# Xmas_A_board.net
KiCad netlist of a schematic drawn in EAGLE
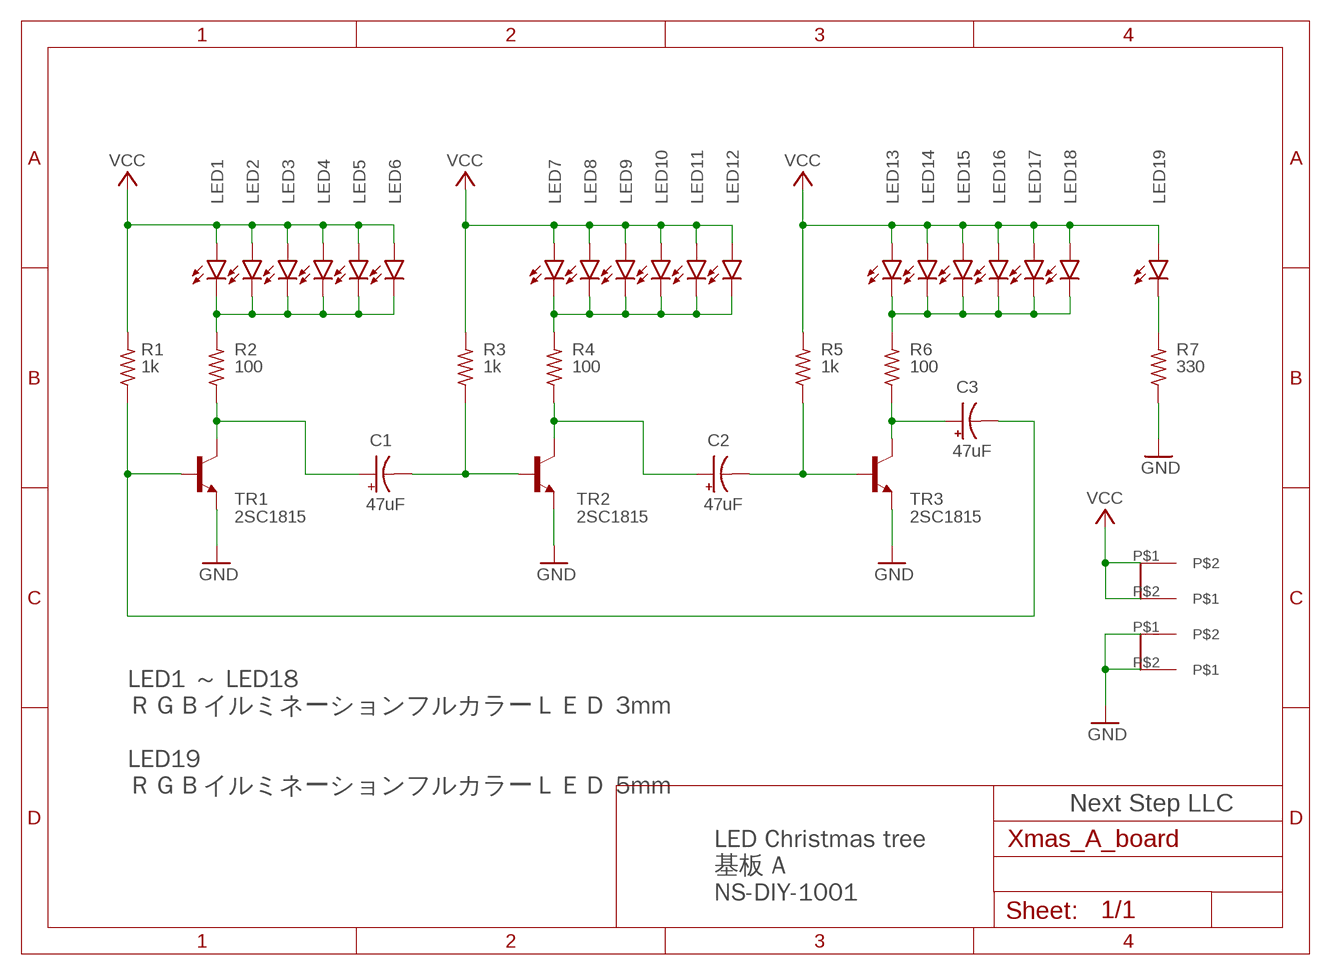
[diagram p0: schematic, sheet 1]

(export (version "E")
  (design (tool "Eeschema 10.0.6"))
  (components
    (comp (ref "C1")
      (value "47uF")
      (footprint "eagle-import:E2-4")
      (libsource (lib "eagle-import") (part "CPOL-USE2-4"))
    )
    (comp (ref "C2")
      (value "47uF")
      (footprint "eagle-import:E2-4")
      (libsource (lib "eagle-import") (part "CPOL-USE2-4"))
    )
    (comp (ref "C3")
      (value "47uF")
      (footprint "eagle-import:E2-4")
      (libsource (lib "eagle-import") (part "CPOL-USE2-4"))
    )
    (comp (ref "LED1")
      (value "LED3MM")
      (footprint "eagle-import:LED3MM")
      (libsource (lib "eagle-import") (part "LED3MM"))
    )
    (comp (ref "LED2")
      (value "LED3MM")
      (footprint "eagle-import:LED3MM")
      (libsource (lib "eagle-import") (part "LED3MM"))
    )
    (comp (ref "LED3")
      (value "LED3MM")
      (footprint "eagle-import:LED3MM")
      (libsource (lib "eagle-import") (part "LED3MM"))
    )
    (comp (ref "LED4")
      (value "LED3MM")
      (footprint "eagle-import:LED3MM")
      (libsource (lib "eagle-import") (part "LED3MM"))
    )
    (comp (ref "LED5")
      (value "LED3MM")
      (footprint "eagle-import:LED3MM")
      (libsource (lib "eagle-import") (part "LED3MM"))
    )
    (comp (ref "LED6")
      (value "LED3MM")
      (footprint "eagle-import:LED3MM")
      (libsource (lib "eagle-import") (part "LED3MM"))
    )
    (comp (ref "LED7")
      (value "LED3MM")
      (footprint "eagle-import:LED3MM")
      (libsource (lib "eagle-import") (part "LED3MM"))
    )
    (comp (ref "LED8")
      (value "LED3MM")
      (footprint "eagle-import:LED3MM")
      (libsource (lib "eagle-import") (part "LED3MM"))
    )
    (comp (ref "LED9")
      (value "LED3MM")
      (footprint "eagle-import:LED3MM")
      (libsource (lib "eagle-import") (part "LED3MM"))
    )
    (comp (ref "LED10")
      (value "LED3MM")
      (footprint "eagle-import:LED3MM")
      (libsource (lib "eagle-import") (part "LED3MM"))
    )
    (comp (ref "LED11")
      (value "LED3MM")
      (footprint "eagle-import:LED3MM")
      (libsource (lib "eagle-import") (part "LED3MM"))
    )
    (comp (ref "LED12")
      (value "LED3MM")
      (footprint "eagle-import:LED3MM")
      (libsource (lib "eagle-import") (part "LED3MM"))
    )
    (comp (ref "LED13")
      (value "LED3MM")
      (footprint "eagle-import:LED3MM")
      (libsource (lib "eagle-import") (part "LED3MM"))
    )
    (comp (ref "LED14")
      (value "LED3MM")
      (footprint "eagle-import:LED3MM")
      (libsource (lib "eagle-import") (part "LED3MM"))
    )
    (comp (ref "LED15")
      (value "LED3MM")
      (footprint "eagle-import:LED3MM")
      (libsource (lib "eagle-import") (part "LED3MM"))
    )
    (comp (ref "LED16")
      (value "LED3MM")
      (footprint "eagle-import:LED3MM")
      (libsource (lib "eagle-import") (part "LED3MM"))
    )
    (comp (ref "LED17")
      (value "LED3MM")
      (footprint "eagle-import:LED3MM")
      (libsource (lib "eagle-import") (part "LED3MM"))
    )
    (comp (ref "LED18")
      (value "LED3MM")
      (footprint "eagle-import:LED3MM")
      (libsource (lib "eagle-import") (part "LED3MM"))
    )
    (comp (ref "LED19")
      (value "LED5MM")
      (footprint "eagle-import:LED5MM")
      (libsource (lib "eagle-import") (part "LED5MM"))
    )
    (comp (ref "R1")
      (value "1k")
      (footprint "eagle-import:0204_7")
      (libsource (lib "eagle-import") (part "R-US_0204/7"))
    )
    (comp (ref "R2")
      (value "100")
      (footprint "eagle-import:0204_7")
      (libsource (lib "eagle-import") (part "R-US_0204/7"))
    )
    (comp (ref "R3")
      (value "1k")
      (footprint "eagle-import:0204_7")
      (libsource (lib "eagle-import") (part "R-US_0204/7"))
    )
    (comp (ref "R4")
      (value "100")
      (footprint "eagle-import:0204_7")
      (libsource (lib "eagle-import") (part "R-US_0204/7"))
    )
    (comp (ref "R5")
      (value "1k")
      (footprint "eagle-import:0204_7")
      (libsource (lib "eagle-import") (part "R-US_0204/7"))
    )
    (comp (ref "R6")
      (value "100")
      (footprint "eagle-import:0204_7")
      (libsource (lib "eagle-import") (part "R-US_0204/7"))
    )
    (comp (ref "R7")
      (value "330")
      (footprint "eagle-import:0204_7")
      (libsource (lib "eagle-import") (part "R-US_0204/7"))
    )
    (comp (ref "TR1")
      (value "2SC1815")
      (footprint "eagle-import:TO92-ECB")
      (libsource (lib "eagle-import") (part "2SC1815"))
    )
    (comp (ref "TR2")
      (value "2SC1815")
      (footprint "eagle-import:TO92-ECB")
      (libsource (lib "eagle-import") (part "2SC1815"))
    )
    (comp (ref "TR3")
      (value "2SC1815")
      (footprint "eagle-import:TO92-ECB")
      (libsource (lib "eagle-import") (part "2SC1815"))
    )
    (comp (ref "U$1")
      (value "XMAS_POWER")
      (footprint "eagle-import:XMAS_POWER")
      (libsource (lib "eagle-import") (part "XMAS_POWER"))
    )
    (comp (ref "U$2")
      (value "XMAS_POWER")
      (footprint "eagle-import:XMAS_POWER")
      (libsource (lib "eagle-import") (part "XMAS_POWER"))
    )
  )
  (nets
    (net (code "1") (name "GND") (class "Default")
      (node (ref "R7") (pin "1") (pinfunction "1_1") (pintype "passive"))
      (node (ref "TR1") (pin "E") (pinfunction "E_E") (pintype "passive"))
      (node (ref "TR2") (pin "E") (pinfunction "E_E") (pintype "passive"))
      (node (ref "TR3") (pin "E") (pinfunction "E_E") (pintype "passive"))
      (node (ref "U$1") (pin "P$1") (pinfunction "P$2_P$1") (pintype "bidirectional"))
      (node (ref "U$1") (pin "P$2") (pinfunction "P$1_P$2") (pintype "bidirectional"))
    )
    (net (code "2") (name "Net-(C1-Pad+)") (class "Default")
      (node (ref "C1") (pin "+") (pinfunction "+_+") (pintype "passive"))
      (node (ref "R2") (pin "1") (pinfunction "1_1") (pintype "passive"))
      (node (ref "TR1") (pin "C") (pinfunction "C_C") (pintype "passive"))
    )
    (net (code "3") (name "Net-(C1-Pad-)") (class "Default")
      (node (ref "C1") (pin "-") (pinfunction "-_-") (pintype "passive"))
      (node (ref "R3") (pin "1") (pinfunction "1_1") (pintype "passive"))
      (node (ref "TR2") (pin "B") (pinfunction "B_B") (pintype "passive"))
    )
    (net (code "4") (name "Net-(C2-Pad+)") (class "Default")
      (node (ref "C2") (pin "+") (pinfunction "+_+") (pintype "passive"))
      (node (ref "R4") (pin "1") (pinfunction "1_1") (pintype "passive"))
      (node (ref "TR2") (pin "C") (pinfunction "C_C") (pintype "passive"))
    )
    (net (code "5") (name "Net-(C2-Pad-)") (class "Default")
      (node (ref "C2") (pin "-") (pinfunction "-_-") (pintype "passive"))
      (node (ref "R5") (pin "1") (pinfunction "1_1") (pintype "passive"))
      (node (ref "TR3") (pin "B") (pinfunction "B_B") (pintype "passive"))
    )
    (net (code "6") (name "Net-(C3-Pad+)") (class "Default")
      (node (ref "C3") (pin "+") (pinfunction "+_+") (pintype "passive"))
      (node (ref "R6") (pin "1") (pinfunction "1_1") (pintype "passive"))
      (node (ref "TR3") (pin "C") (pinfunction "C_C") (pintype "passive"))
    )
    (net (code "7") (name "Net-(C3-Pad-)") (class "Default")
      (node (ref "C3") (pin "-") (pinfunction "-_-") (pintype "passive"))
      (node (ref "R1") (pin "1") (pinfunction "1_1") (pintype "passive"))
      (node (ref "TR1") (pin "B") (pinfunction "B_B") (pintype "passive"))
    )
    (net (code "8") (name "Net-(LED1-C)") (class "Default")
      (node (ref "LED1") (pin "K") (pinfunction "C_K") (pintype "passive"))
      (node (ref "LED2") (pin "K") (pinfunction "C_K") (pintype "passive"))
      (node (ref "LED3") (pin "K") (pinfunction "C_K") (pintype "passive"))
      (node (ref "LED4") (pin "K") (pinfunction "C_K") (pintype "passive"))
      (node (ref "LED5") (pin "K") (pinfunction "C_K") (pintype "passive"))
      (node (ref "LED6") (pin "K") (pinfunction "C_K") (pintype "passive"))
      (node (ref "R2") (pin "2") (pinfunction "2_2") (pintype "passive"))
    )
    (net (code "9") (name "Net-(LED10-C)") (class "Default")
      (node (ref "LED10") (pin "K") (pinfunction "C_K") (pintype "passive"))
      (node (ref "LED11") (pin "K") (pinfunction "C_K") (pintype "passive"))
      (node (ref "LED12") (pin "K") (pinfunction "C_K") (pintype "passive"))
      (node (ref "LED7") (pin "K") (pinfunction "C_K") (pintype "passive"))
      (node (ref "LED8") (pin "K") (pinfunction "C_K") (pintype "passive"))
      (node (ref "LED9") (pin "K") (pinfunction "C_K") (pintype "passive"))
      (node (ref "R4") (pin "2") (pinfunction "2_2") (pintype "passive"))
    )
    (net (code "10") (name "Net-(LED13-C)") (class "Default")
      (node (ref "LED13") (pin "K") (pinfunction "C_K") (pintype "passive"))
      (node (ref "LED14") (pin "K") (pinfunction "C_K") (pintype "passive"))
      (node (ref "LED15") (pin "K") (pinfunction "C_K") (pintype "passive"))
      (node (ref "LED16") (pin "K") (pinfunction "C_K") (pintype "passive"))
      (node (ref "LED17") (pin "K") (pinfunction "C_K") (pintype "passive"))
      (node (ref "LED18") (pin "K") (pinfunction "C_K") (pintype "passive"))
      (node (ref "R6") (pin "2") (pinfunction "2_2") (pintype "passive"))
    )
    (net (code "11") (name "Net-(LED19-C)") (class "Default")
      (node (ref "LED19") (pin "K") (pinfunction "C_K") (pintype "passive"))
      (node (ref "R7") (pin "2") (pinfunction "2_2") (pintype "passive"))
    )
    (net (code "12") (name "VCC") (class "Default")
      (node (ref "LED1") (pin "A") (pinfunction "A_A") (pintype "passive"))
      (node (ref "LED10") (pin "A") (pinfunction "A_A") (pintype "passive"))
      (node (ref "LED11") (pin "A") (pinfunction "A_A") (pintype "passive"))
      (node (ref "LED12") (pin "A") (pinfunction "A_A") (pintype "passive"))
      (node (ref "LED13") (pin "A") (pinfunction "A_A") (pintype "passive"))
      (node (ref "LED14") (pin "A") (pinfunction "A_A") (pintype "passive"))
      (node (ref "LED15") (pin "A") (pinfunction "A_A") (pintype "passive"))
      (node (ref "LED16") (pin "A") (pinfunction "A_A") (pintype "passive"))
      (node (ref "LED17") (pin "A") (pinfunction "A_A") (pintype "passive"))
      (node (ref "LED18") (pin "A") (pinfunction "A_A") (pintype "passive"))
      (node (ref "LED19") (pin "A") (pinfunction "A_A") (pintype "passive"))
      (node (ref "LED2") (pin "A") (pinfunction "A_A") (pintype "passive"))
      (node (ref "LED3") (pin "A") (pinfunction "A_A") (pintype "passive"))
      (node (ref "LED4") (pin "A") (pinfunction "A_A") (pintype "passive"))
      (node (ref "LED5") (pin "A") (pinfunction "A_A") (pintype "passive"))
      (node (ref "LED6") (pin "A") (pinfunction "A_A") (pintype "passive"))
      (node (ref "LED7") (pin "A") (pinfunction "A_A") (pintype "passive"))
      (node (ref "LED8") (pin "A") (pinfunction "A_A") (pintype "passive"))
      (node (ref "LED9") (pin "A") (pinfunction "A_A") (pintype "passive"))
      (node (ref "R1") (pin "2") (pinfunction "2_2") (pintype "passive"))
      (node (ref "R3") (pin "2") (pinfunction "2_2") (pintype "passive"))
      (node (ref "R5") (pin "2") (pinfunction "2_2") (pintype "passive"))
      (node (ref "U$2") (pin "P$1") (pinfunction "P$2_P$1") (pintype "bidirectional"))
      (node (ref "U$2") (pin "P$2") (pinfunction "P$1_P$2") (pintype "bidirectional"))
    )
  )
)
